# dwm.net
KiCad netlist of a schematic drawn in Altium Designer
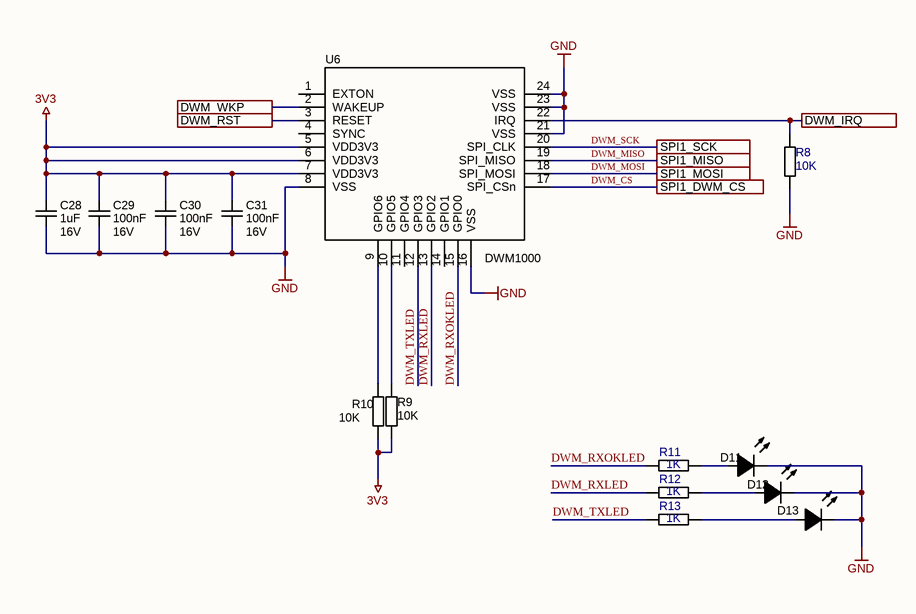
[diagram p0: dwm.SchDoc]

(export (version "E")
  (design (tool "Eeschema 10.0.6"))
  (components
    (comp (ref "C28")
      (value "1uF")
      (footprint "C0603")
      (fields (field (name "VOLTAGE") "16V") (field (name "Comment") "C0603"))
      (libsource (lib "DZ_LIB") (part "C0603"))
    )
    (comp (ref "C29")
      (value "100nF")
      (footprint "C0603")
      (fields (field (name "VOLTAGE") "16V") (field (name "Comment") "C0603"))
      (libsource (lib "DZ_LIB") (part "C0603"))
    )
    (comp (ref "C30")
      (value "100nF")
      (footprint "C0603")
      (fields (field (name "VOLTAGE") "16V") (field (name "Comment") "C0603"))
      (libsource (lib "DZ_LIB") (part "C0603"))
    )
    (comp (ref "C31")
      (value "100nF")
      (footprint "C0603")
      (fields (field (name "VOLTAGE") "16V") (field (name "Comment") "C0603"))
      (libsource (lib "DZ_LIB") (part "C0603"))
    )
    (comp (ref "D11")
      (value "LED0805")
      (footprint "LED0805")
      (description "LED SMD 0805 K1A2")
      (libsource (lib "DZ_LIB") (part "LED0805"))
    )
    (comp (ref "D12")
      (value "LED0805")
      (footprint "LED0805")
      (description "LED SMD 0805 K1A2")
      (libsource (lib "DZ_LIB") (part "LED0805"))
    )
    (comp (ref "D13")
      (value "LED0805")
      (footprint "LED0805")
      (description "LED SMD 0805 K1A2")
      (libsource (lib "DZ_LIB") (part "LED0805"))
    )
    (comp (ref "R8") (value "10K") (footprint "SMD0603") (libsource (lib "DZ_LIB") (part "R0603")))
    (comp (ref "R9")
      (value "10K")
      (footprint "SMD0603")
      (fields (field (name "Comment") "R0603"))
      (libsource (lib "") (part "R0603_2"))
    )
    (comp (ref "R10")
      (value "10K")
      (footprint "SMD0603")
      (fields (field (name "Comment") "R0603"))
      (libsource (lib "") (part "R0603_2"))
    )
    (comp (ref "R11") (value "1K") (footprint "SMD0603") (libsource (lib "") (part "R0603_1")))
    (comp (ref "R12") (value "1K") (footprint "SMD0603") (libsource (lib "") (part "R0603_1")))
    (comp (ref "R13") (value "1K") (footprint "SMD0603") (libsource (lib "") (part "R0603_1")))
    (comp (ref "U6")
      (value "DWM1000")
      (footprint "DWM1000")
      (description "MOD IEEE802.15.4-2011 UWB TXRX")
      (fields (field (name "MANUFACTURER") "Decawave Limited"))
      (libsource (lib "DZ_LIB") (part "DWM1000"))
    )
  )
  (nets
    (net (code "1") (name "/DWM_CS") (class "Default")
      (node (ref "U6") (pin "17") (pinfunction "SPI_CSn_17") (pintype "passive"))
    )
    (net (code "2") (name "/DWM_IRQ") (class "Default")
      (node (ref "R8") (pin "2") (pinfunction "2_2") (pintype "passive"))
      (node (ref "U6") (pin "22") (pinfunction "IRQ_22") (pintype "passive"))
    )
    (net (code "3") (name "/DWM_MISO") (class "Default")
      (node (ref "U6") (pin "19") (pinfunction "SPI_MISO_19") (pintype "passive"))
    )
    (net (code "4") (name "/DWM_MOSI") (class "Default")
      (node (ref "U6") (pin "18") (pinfunction "SPI_MOSI_18") (pintype "passive"))
    )
    (net (code "5") (name "/DWM_RST") (class "Default")
      (node (ref "U6") (pin "3") (pinfunction "RESET_3") (pintype "passive"))
    )
    (net (code "6") (name "/DWM_RXLED") (class "Default")
      (node (ref "R12") (pin "2") (pinfunction "2_2") (pintype "passive"))
      (node (ref "U6") (pin "13") (pinfunction "GPIO2_13") (pintype "passive"))
    )
    (net (code "7") (name "/DWM_RXOKLED") (class "Default")
      (node (ref "R11") (pin "2") (pinfunction "2_2") (pintype "passive"))
      (node (ref "U6") (pin "15") (pinfunction "GPIO0_15") (pintype "passive"))
    )
    (net (code "8") (name "/DWM_SCK") (class "Default")
      (node (ref "U6") (pin "20") (pinfunction "SPI_CLK_20") (pintype "passive"))
    )
    (net (code "9") (name "/DWM_TXLED") (class "Default")
      (node (ref "R13") (pin "2") (pinfunction "2_2") (pintype "passive"))
      (node (ref "U6") (pin "12") (pinfunction "GPIO3_12") (pintype "passive"))
    )
    (net (code "10") (name "/DWM_WKP") (class "Default")
      (node (ref "U6") (pin "2") (pinfunction "WAKEUP_2") (pintype "passive"))
    )
    (net (code "11") (name "3V3") (class "Default")
      (node (ref "C28") (pin "1") (pinfunction "1_1") (pintype "passive"))
      (node (ref "C29") (pin "1") (pinfunction "1_1") (pintype "passive"))
      (node (ref "C30") (pin "1") (pinfunction "1_1") (pintype "passive"))
      (node (ref "C31") (pin "1") (pinfunction "1_1") (pintype "passive"))
      (node (ref "R10") (pin "2") (pinfunction "2_2") (pintype "passive"))
      (node (ref "R9") (pin "2") (pinfunction "2_2") (pintype "passive"))
      (node (ref "U6") (pin "5") (pinfunction "VDD3V3_5") (pintype "passive"))
      (node (ref "U6") (pin "6") (pinfunction "VDD3V3_6") (pintype "passive"))
      (node (ref "U6") (pin "7") (pinfunction "VDD3V3_7") (pintype "passive"))
    )
    (net (code "12") (name "GND") (class "Default")
      (node (ref "C28") (pin "2") (pinfunction "2_2") (pintype "passive"))
      (node (ref "C29") (pin "2") (pinfunction "2_2") (pintype "passive"))
      (node (ref "C30") (pin "2") (pinfunction "2_2") (pintype "passive"))
      (node (ref "C31") (pin "2") (pinfunction "2_2") (pintype "passive"))
      (node (ref "D11") (pin "1") (pinfunction "K_1") (pintype "passive"))
      (node (ref "D12") (pin "1") (pinfunction "K_1") (pintype "passive"))
      (node (ref "D13") (pin "1") (pinfunction "K_1") (pintype "passive"))
      (node (ref "R8") (pin "1") (pinfunction "1_1") (pintype "passive"))
      (node (ref "U6") (pin "16") (pinfunction "VSS_16") (pintype "passive"))
      (node (ref "U6") (pin "21") (pinfunction "VSS_21") (pintype "passive"))
      (node (ref "U6") (pin "23") (pinfunction "VSS_23") (pintype "passive"))
      (node (ref "U6") (pin "24") (pinfunction "VSS_24") (pintype "passive"))
      (node (ref "U6") (pin "8") (pinfunction "VSS_8") (pintype "passive"))
    )
    (net (code "13") (name "Net-(D11-A)") (class "Default")
      (node (ref "D11") (pin "2") (pinfunction "A_2") (pintype "passive"))
      (node (ref "R11") (pin "1") (pinfunction "1_1") (pintype "passive"))
    )
    (net (code "14") (name "Net-(D12-A)") (class "Default")
      (node (ref "D12") (pin "2") (pinfunction "A_2") (pintype "passive"))
      (node (ref "R12") (pin "1") (pinfunction "1_1") (pintype "passive"))
    )
    (net (code "15") (name "Net-(D13-A)") (class "Default")
      (node (ref "D13") (pin "2") (pinfunction "A_2") (pintype "passive"))
      (node (ref "R13") (pin "1") (pinfunction "1_1") (pintype "passive"))
    )
    (net (code "16") (name "Net-(U6-GPIO5)") (class "Default")
      (node (ref "R9") (pin "1") (pinfunction "1_1") (pintype "passive"))
      (node (ref "U6") (pin "10") (pinfunction "GPIO5_10") (pintype "passive"))
    )
    (net (code "17") (name "Net-(U6-GPIO6)") (class "Default")
      (node (ref "R10") (pin "1") (pinfunction "1_1") (pintype "passive"))
      (node (ref "U6") (pin "9") (pinfunction "GPIO6_9") (pintype "passive"))
    )
    (net (code "18") (name "unconnected-(U6-EXTON-Pad1)") (class "Default")
      (node (ref "U6") (pin "1") (pinfunction "EXTON_1") (pintype "passive"))
    )
    (net (code "19") (name "unconnected-(U6-GPIO1-Pad14)") (class "Default")
      (node (ref "U6") (pin "14") (pinfunction "GPIO1_14") (pintype "passive"))
    )
    (net (code "20") (name "unconnected-(U6-GPIO4-Pad11)") (class "Default")
      (node (ref "U6") (pin "11") (pinfunction "GPIO4_11") (pintype "passive"))
    )
    (net (code "21") (name "unconnected-(U6-SYNC-Pad4)") (class "Default")
      (node (ref "U6") (pin "4") (pinfunction "SYNC_4") (pintype "passive"))
    )
  )
)
